# MOM-analog-ins_v06.net
KiCad netlist of a schematic drawn in EAGLE
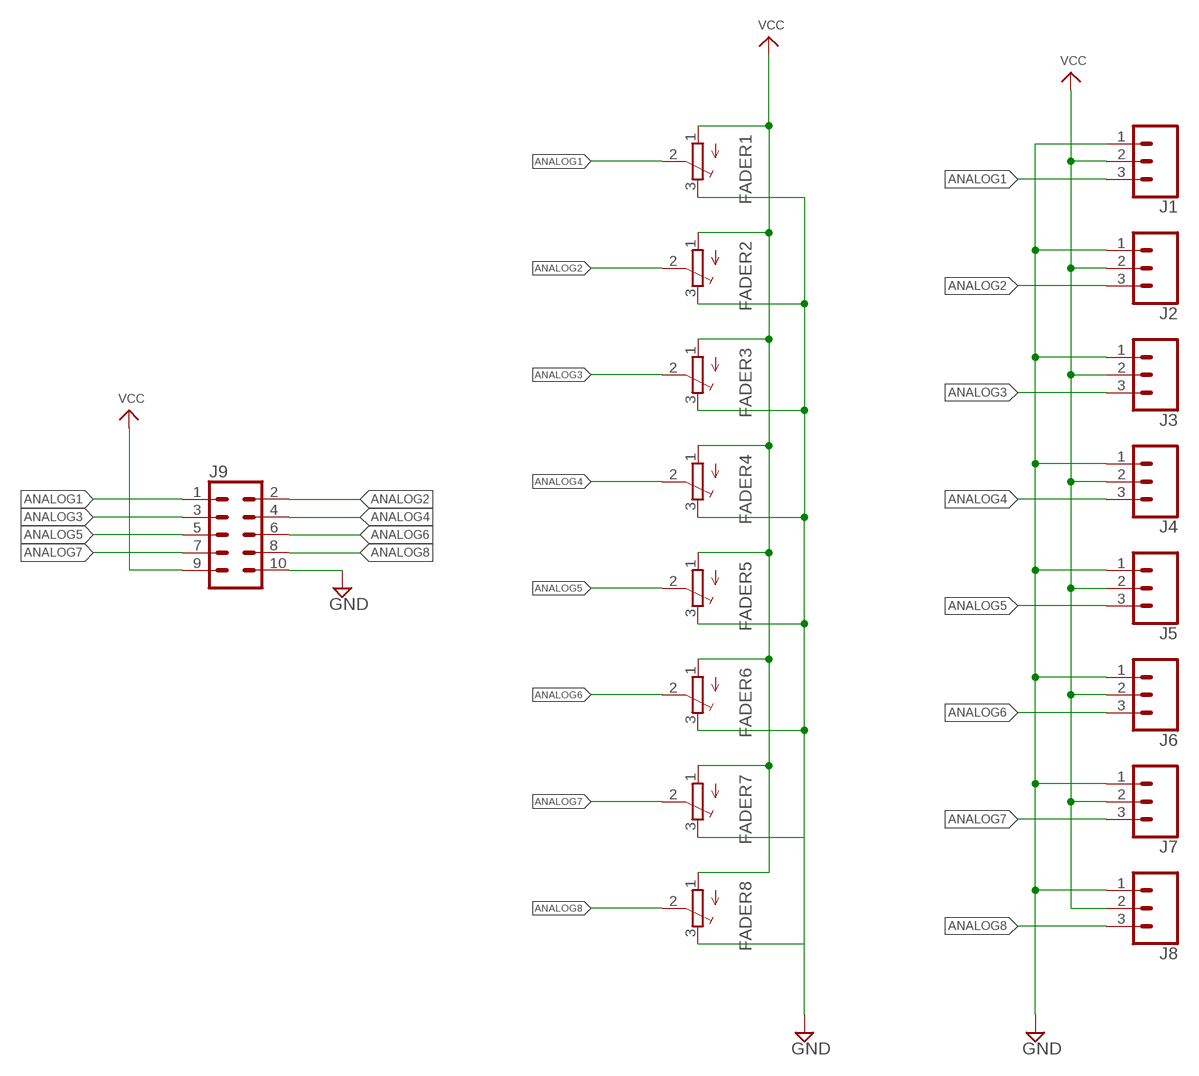
[diagram p0: schematic, sheet 1]

(export (version "E")
  (design (tool "Eeschema 10.0.6"))
  (components
    (comp (ref "FADER1")
      (value "TRIMPOT3386")
      (footprint "eagle-import:TRIM-3386")
      (libsource (lib "eagle-import") (part "TRIMPOT3386"))
    )
    (comp (ref "FADER2")
      (value "TRIMPOT3386")
      (footprint "eagle-import:TRIM-3386")
      (libsource (lib "eagle-import") (part "TRIMPOT3386"))
    )
    (comp (ref "FADER3")
      (value "TRIMPOT3386")
      (footprint "eagle-import:TRIM-3386")
      (libsource (lib "eagle-import") (part "TRIMPOT3386"))
    )
    (comp (ref "FADER4")
      (value "TRIMPOT3386")
      (footprint "eagle-import:TRIM-3386")
      (libsource (lib "eagle-import") (part "TRIMPOT3386"))
    )
    (comp (ref "FADER5")
      (value "TRIMPOT3386")
      (footprint "eagle-import:TRIM-3386")
      (libsource (lib "eagle-import") (part "TRIMPOT3386"))
    )
    (comp (ref "FADER6")
      (value "TRIMPOT3386")
      (footprint "eagle-import:TRIM-3386")
      (libsource (lib "eagle-import") (part "TRIMPOT3386"))
    )
    (comp (ref "FADER7")
      (value "TRIMPOT3386")
      (footprint "eagle-import:TRIM-3386")
      (libsource (lib "eagle-import") (part "TRIMPOT3386"))
    )
    (comp (ref "FADER8")
      (value "TRIMPOT3386")
      (footprint "eagle-import:TRIM-3386")
      (libsource (lib "eagle-import") (part "TRIMPOT3386"))
    )
    (comp (ref "J1")
      (value "CONN_03LOCK")
      (footprint "eagle-import:1X03_LOCK")
      (libsource (lib "eagle-import") (part "CONN_03LOCK"))
    )
    (comp (ref "J2")
      (value "CONN_03LOCK")
      (footprint "eagle-import:1X03_LOCK")
      (libsource (lib "eagle-import") (part "CONN_03LOCK"))
    )
    (comp (ref "J3")
      (value "CONN_03LOCK")
      (footprint "eagle-import:1X03_LOCK")
      (libsource (lib "eagle-import") (part "CONN_03LOCK"))
    )
    (comp (ref "J4")
      (value "CONN_03LOCK")
      (footprint "eagle-import:1X03_LOCK")
      (libsource (lib "eagle-import") (part "CONN_03LOCK"))
    )
    (comp (ref "J5")
      (value "CONN_03LOCK")
      (footprint "eagle-import:1X03_LOCK")
      (libsource (lib "eagle-import") (part "CONN_03LOCK"))
    )
    (comp (ref "J6")
      (value "CONN_03LOCK")
      (footprint "eagle-import:1X03_LOCK")
      (libsource (lib "eagle-import") (part "CONN_03LOCK"))
    )
    (comp (ref "J7")
      (value "CONN_03LOCK")
      (footprint "eagle-import:1X03_LOCK")
      (libsource (lib "eagle-import") (part "CONN_03LOCK"))
    )
    (comp (ref "J8")
      (value "CONN_03LOCK")
      (footprint "eagle-import:1X03_LOCK")
      (libsource (lib "eagle-import") (part "CONN_03LOCK"))
    )
    (comp (ref "J9")
      (value "CONN_05X2SHD_LOCK")
      (footprint "eagle-import:2X5-SHROUDED_LOCK")
      (libsource (lib "eagle-import") (part "CONN_05X2SHD_LOCK"))
    )
  )
  (nets
    (net (code "1") (name "ANALOG1") (class "Default")
      (node (ref "FADER1") (pin "2") (pinfunction "S_2") (pintype "passive"))
      (node (ref "J1") (pin "3") (pinfunction "3_3") (pintype "passive"))
      (node (ref "J9") (pin "1") (pinfunction "1_1") (pintype "passive"))
    )
    (net (code "2") (name "ANALOG2") (class "Default")
      (node (ref "FADER2") (pin "2") (pinfunction "S_2") (pintype "passive"))
      (node (ref "J2") (pin "3") (pinfunction "3_3") (pintype "passive"))
      (node (ref "J9") (pin "2") (pinfunction "2_2") (pintype "passive"))
    )
    (net (code "3") (name "ANALOG3") (class "Default")
      (node (ref "FADER3") (pin "2") (pinfunction "S_2") (pintype "passive"))
      (node (ref "J3") (pin "3") (pinfunction "3_3") (pintype "passive"))
      (node (ref "J9") (pin "3") (pinfunction "3_3") (pintype "passive"))
    )
    (net (code "4") (name "ANALOG4") (class "Default")
      (node (ref "FADER4") (pin "2") (pinfunction "S_2") (pintype "passive"))
      (node (ref "J4") (pin "3") (pinfunction "3_3") (pintype "passive"))
      (node (ref "J9") (pin "4") (pinfunction "4_4") (pintype "passive"))
    )
    (net (code "5") (name "ANALOG5") (class "Default")
      (node (ref "FADER5") (pin "2") (pinfunction "S_2") (pintype "passive"))
      (node (ref "J5") (pin "3") (pinfunction "3_3") (pintype "passive"))
      (node (ref "J9") (pin "5") (pinfunction "5_5") (pintype "passive"))
    )
    (net (code "6") (name "ANALOG6") (class "Default")
      (node (ref "FADER6") (pin "2") (pinfunction "S_2") (pintype "passive"))
      (node (ref "J6") (pin "3") (pinfunction "3_3") (pintype "passive"))
      (node (ref "J9") (pin "6") (pinfunction "6_6") (pintype "passive"))
    )
    (net (code "7") (name "ANALOG7") (class "Default")
      (node (ref "FADER7") (pin "2") (pinfunction "S_2") (pintype "passive"))
      (node (ref "J7") (pin "3") (pinfunction "3_3") (pintype "passive"))
      (node (ref "J9") (pin "7") (pinfunction "7_7") (pintype "passive"))
    )
    (net (code "8") (name "ANALOG8") (class "Default")
      (node (ref "FADER8") (pin "2") (pinfunction "S_2") (pintype "passive"))
      (node (ref "J8") (pin "3") (pinfunction "3_3") (pintype "passive"))
      (node (ref "J9") (pin "8") (pinfunction "8_8") (pintype "passive"))
    )
    (net (code "9") (name "GND") (class "Default")
      (node (ref "FADER1") (pin "3") (pinfunction "E_3") (pintype "passive"))
      (node (ref "FADER2") (pin "3") (pinfunction "E_3") (pintype "passive"))
      (node (ref "FADER3") (pin "3") (pinfunction "E_3") (pintype "passive"))
      (node (ref "FADER4") (pin "3") (pinfunction "E_3") (pintype "passive"))
      (node (ref "FADER5") (pin "3") (pinfunction "E_3") (pintype "passive"))
      (node (ref "FADER6") (pin "3") (pinfunction "E_3") (pintype "passive"))
      (node (ref "FADER7") (pin "3") (pinfunction "E_3") (pintype "passive"))
      (node (ref "FADER8") (pin "3") (pinfunction "E_3") (pintype "passive"))
      (node (ref "J1") (pin "1") (pinfunction "1_1") (pintype "passive"))
      (node (ref "J2") (pin "1") (pinfunction "1_1") (pintype "passive"))
      (node (ref "J3") (pin "1") (pinfunction "1_1") (pintype "passive"))
      (node (ref "J4") (pin "1") (pinfunction "1_1") (pintype "passive"))
      (node (ref "J5") (pin "1") (pinfunction "1_1") (pintype "passive"))
      (node (ref "J6") (pin "1") (pinfunction "1_1") (pintype "passive"))
      (node (ref "J7") (pin "1") (pinfunction "1_1") (pintype "passive"))
      (node (ref "J8") (pin "1") (pinfunction "1_1") (pintype "passive"))
      (node (ref "J9") (pin "10") (pinfunction "10_10") (pintype "passive"))
    )
    (net (code "10") (name "VCC") (class "Default")
      (node (ref "FADER1") (pin "1") (pinfunction "A_1") (pintype "passive"))
      (node (ref "FADER2") (pin "1") (pinfunction "A_1") (pintype "passive"))
      (node (ref "FADER3") (pin "1") (pinfunction "A_1") (pintype "passive"))
      (node (ref "FADER4") (pin "1") (pinfunction "A_1") (pintype "passive"))
      (node (ref "FADER5") (pin "1") (pinfunction "A_1") (pintype "passive"))
      (node (ref "FADER6") (pin "1") (pinfunction "A_1") (pintype "passive"))
      (node (ref "FADER7") (pin "1") (pinfunction "A_1") (pintype "passive"))
      (node (ref "FADER8") (pin "1") (pinfunction "A_1") (pintype "passive"))
      (node (ref "J1") (pin "2") (pinfunction "2_2") (pintype "passive"))
      (node (ref "J2") (pin "2") (pinfunction "2_2") (pintype "passive"))
      (node (ref "J3") (pin "2") (pinfunction "2_2") (pintype "passive"))
      (node (ref "J4") (pin "2") (pinfunction "2_2") (pintype "passive"))
      (node (ref "J5") (pin "2") (pinfunction "2_2") (pintype "passive"))
      (node (ref "J6") (pin "2") (pinfunction "2_2") (pintype "passive"))
      (node (ref "J7") (pin "2") (pinfunction "2_2") (pintype "passive"))
      (node (ref "J8") (pin "2") (pinfunction "2_2") (pintype "passive"))
      (node (ref "J9") (pin "9") (pinfunction "9_9") (pintype "passive"))
    )
  )
)
